# poesp_1_0.net
KiCad netlist of a schematic drawn in EAGLE
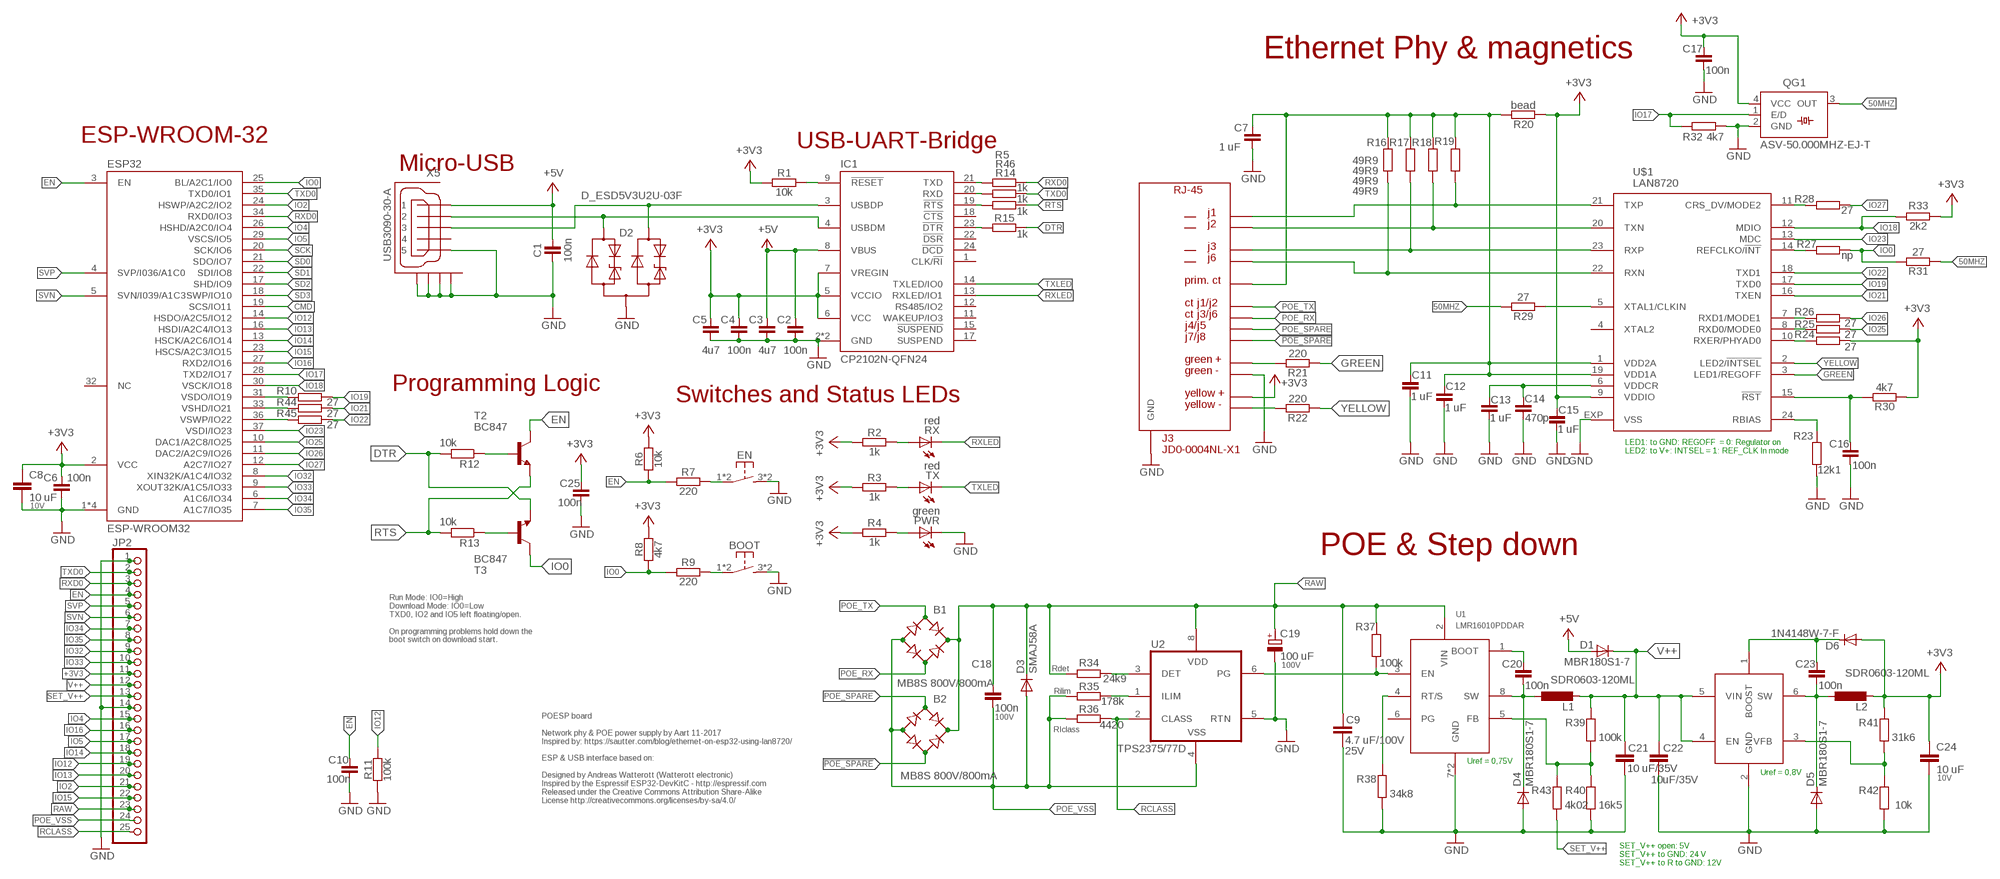
[diagram p0: schematic, sheet 1]

(export (version "E")
  (design (tool "Eeschema 10.0.6"))
  (components
    (comp (ref "B1")
      (value "MB8S 800V/800mA")
      (footprint "eagle-import:MBS")
      (libsource (lib "eagle-import") (part "BS10"))
    )
    (comp (ref "B2")
      (value "MB8S 800V/800mA")
      (footprint "eagle-import:MBS")
      (libsource (lib "eagle-import") (part "BS10"))
    )
    (comp (ref "BOOT")
      (value "SW-TACTILE-PTS840P")
      (footprint "eagle-import:PTS840P")
      (libsource (lib "eagle-import") (part "SW-TACTILE-PTS840P"))
    )
    (comp (ref "C1")
      (value "100n")
      (footprint "eagle-import:C0603")
      (libsource (lib "eagle-import") (part "CAPACITOR-0603"))
    )
    (comp (ref "C2")
      (value "100n")
      (footprint "eagle-import:C0603")
      (libsource (lib "eagle-import") (part "CAPACITOR-0603"))
    )
    (comp (ref "C3")
      (value "4u7")
      (footprint "eagle-import:C0805")
      (libsource (lib "eagle-import") (part "CAPACITOR-0805"))
    )
    (comp (ref "C4")
      (value "100n")
      (footprint "eagle-import:C0603")
      (libsource (lib "eagle-import") (part "CAPACITOR-0603"))
    )
    (comp (ref "C5")
      (value "4u7")
      (footprint "eagle-import:C0805")
      (libsource (lib "eagle-import") (part "CAPACITOR-0805"))
    )
    (comp (ref "C6")
      (value "100n")
      (footprint "eagle-import:C0603")
      (libsource (lib "eagle-import") (part "CAPACITOR-0603"))
    )
    (comp (ref "C7")
      (value "1 uF")
      (footprint "eagle-import:C0603")
      (libsource (lib "eagle-import") (part "CAPACITOR-0603"))
    )
    (comp (ref "C8")
      (value "10 uF")
      (footprint "eagle-import:C0805K")
      (fields (field (name "VOLTAGE") "10V"))
      (libsource (lib "eagle-import") (part "C-EUC0805K"))
    )
    (comp (ref "C9")
      (value "4.7 uF/100V")
      (footprint "eagle-import:C1210K")
      (fields (field (name "VOLTAGE") "25V"))
      (libsource (lib "eagle-import") (part "C-EUC1210K"))
    )
    (comp (ref "C10")
      (value "100n")
      (footprint "eagle-import:C0603")
      (libsource (lib "eagle-import") (part "CAPACITOR-0603"))
    )
    (comp (ref "C11")
      (value "1 uF")
      (footprint "eagle-import:C0603")
      (libsource (lib "eagle-import") (part "CAPACITOR-0603"))
    )
    (comp (ref "C12")
      (value "1 uF")
      (footprint "eagle-import:C0603")
      (libsource (lib "eagle-import") (part "CAPACITOR-0603"))
    )
    (comp (ref "C13")
      (value "1 uF")
      (footprint "eagle-import:C0603")
      (libsource (lib "eagle-import") (part "CAPACITOR-0603"))
    )
    (comp (ref "C14")
      (value "470p")
      (footprint "eagle-import:C0603")
      (libsource (lib "eagle-import") (part "CAPACITOR-0603"))
    )
    (comp (ref "C15")
      (value "1 uF")
      (footprint "eagle-import:C0603")
      (libsource (lib "eagle-import") (part "CAPACITOR-0603"))
    )
    (comp (ref "C16")
      (value "100n")
      (footprint "eagle-import:C0603")
      (libsource (lib "eagle-import") (part "CAPACITOR-0603"))
    )
    (comp (ref "C17")
      (value "100n")
      (footprint "eagle-import:C0603")
      (libsource (lib "eagle-import") (part "CAPACITOR-0603"))
    )
    (comp (ref "C18")
      (value "100n")
      (footprint "eagle-import:C0603")
      (fields (field (name "VOLTAGE") "100V"))
      (libsource (lib "eagle-import") (part "CAPACITOR-0603"))
    )
    (comp (ref "C19")
      (value "100 uF")
      (footprint "eagle-import:E5-10,5")
      (fields (field (name "VOLTAGE") "100V"))
      (libsource (lib "eagle-import") (part "CPOL-EUE5-10.5"))
    )
    (comp (ref "C20")
      (value "100n")
      (footprint "eagle-import:C0603")
      (libsource (lib "eagle-import") (part "CAPACITOR-0603"))
    )
    (comp (ref "C21")
      (value "10 uF/35V")
      (footprint "eagle-import:C1210K")
      (fields (field (name "VOLTAGE") "25V"))
      (libsource (lib "eagle-import") (part "C-EUC1210K"))
    )
    (comp (ref "C22")
      (value "10uF/35V")
      (footprint "eagle-import:C1210K")
      (fields (field (name "VOLTAGE") "25V"))
      (libsource (lib "eagle-import") (part "C-EUC1210K"))
    )
    (comp (ref "C23")
      (value "100n")
      (footprint "eagle-import:C0603")
      (libsource (lib "eagle-import") (part "CAPACITOR-0603"))
    )
    (comp (ref "C24")
      (value "10 uF")
      (footprint "eagle-import:C0805K")
      (fields (field (name "VOLTAGE") "10V"))
      (libsource (lib "eagle-import") (part "C-EUC0805K"))
    )
    (comp (ref "C25")
      (value "100n")
      (footprint "eagle-import:C0603")
      (libsource (lib "eagle-import") (part "CAPACITOR-0603"))
    )
    (comp (ref "D1")
      (value "MBR180S1-7")
      (footprint "eagle-import:SOD-123_MINI-SMA")
      (libsource (lib "eagle-import") (part "CGRM400-G1"))
    )
    (comp (ref "D2")
      (value "D_ESD5V3U2U-03F")
      (footprint "eagle-import:SOT723")
      (libsource (lib "eagle-import") (part "D_ESD5V3U2U-03F"))
    )
    (comp (ref "D3")
      (value "SMAJ58A")
      (footprint "eagle-import:DO214AC")
      (libsource (lib "eagle-import") (part "DIODE-DO214AC"))
    )
    (comp (ref "D4")
      (value "MBR180S1-7")
      (footprint "eagle-import:SOD-123_MINI-SMA")
      (libsource (lib "eagle-import") (part "CGRM400-G1"))
    )
    (comp (ref "D5")
      (value "MBR180S1-7")
      (footprint "eagle-import:SOD-123_MINI-SMA")
      (libsource (lib "eagle-import") (part "CGRM400-G1"))
    )
    (comp (ref "D6")
      (value "1N4148W-7-F")
      (footprint "eagle-import:SOD-123_MINI-SMA")
      (libsource (lib "eagle-import") (part "CGRM400-G1"))
    )
    (comp (ref "EN")
      (value "SW-TACTILE-PTS840P")
      (footprint "eagle-import:PTS840P")
      (libsource (lib "eagle-import") (part "SW-TACTILE-PTS840P"))
    )
    (comp (ref "ESP32")
      (value "ESP-WROOM32")
      (footprint "eagle-import:ESP-WROOM32")
      (libsource (lib "eagle-import") (part "ESP-WROOM32"))
    )
    (comp (ref "IC1")
      (value "CP2102N-QFN24")
      (footprint "eagle-import:QFN24-PAD")
      (libsource (lib "eagle-import") (part "CP2102N-QFN24"))
    )
    (comp (ref "IC3")
      (value "MCP16301/H")
      (footprint "eagle-import:SOT23-6")
      (libsource (lib "eagle-import") (part "MCP16301/H"))
    )
    (comp (ref "J3")
      (value "JD0-0004NL-X1")
      (footprint "eagle-import:JD0")
      (libsource (lib "eagle-import") (part "JD0-0004NL-X1"))
    )
    (comp (ref "JP2")
      (value "PINHD-1X25")
      (footprint "eagle-import:1X25")
      (libsource (lib "eagle-import") (part "PINHD-1X25"))
    )
    (comp (ref "L1")
      (value "SDR0603-120ML")
      (footprint "eagle-import:POWER-CHOKE_WE-TPC")
      (libsource (lib "eagle-import") (part "L-EUWE-TPC"))
    )
    (comp (ref "L2")
      (value "SDR0603-120ML")
      (footprint "eagle-import:POWER-CHOKE_WE-TPC")
      (libsource (lib "eagle-import") (part "L-EUWE-TPC"))
    )
    (comp (ref "PWR")
      (value "green")
      (footprint "eagle-import:C0603")
      (libsource (lib "eagle-import") (part "LED-0603"))
    )
    (comp (ref "QG1")
      (value "ASV-50.000MHZ-EJ-T")
      (footprint "eagle-import:SM77H")
      (libsource (lib "eagle-import") (part "SM77H"))
    )
    (comp (ref "R1")
      (value "10k")
      (footprint "eagle-import:C0603")
      (libsource (lib "eagle-import") (part "RESISTOR-0603"))
    )
    (comp (ref "R2")
      (value "1k")
      (footprint "eagle-import:C0603")
      (libsource (lib "eagle-import") (part "RESISTOR-0603"))
    )
    (comp (ref "R3")
      (value "1k")
      (footprint "eagle-import:C0603")
      (libsource (lib "eagle-import") (part "RESISTOR-0603"))
    )
    (comp (ref "R4")
      (value "1k")
      (footprint "eagle-import:C0603")
      (libsource (lib "eagle-import") (part "RESISTOR-0603"))
    )
    (comp (ref "R5")
      (value "1k")
      (footprint "eagle-import:C0603")
      (libsource (lib "eagle-import") (part "RESISTOR-0603"))
    )
    (comp (ref "R6")
      (value "10k")
      (footprint "eagle-import:C0603")
      (libsource (lib "eagle-import") (part "RESISTOR-0603"))
    )
    (comp (ref "R7")
      (value "220")
      (footprint "eagle-import:C0603")
      (libsource (lib "eagle-import") (part "RESISTOR-0603"))
    )
    (comp (ref "R8")
      (value "4k7")
      (footprint "eagle-import:C0603")
      (libsource (lib "eagle-import") (part "RESISTOR-0603"))
    )
    (comp (ref "R9")
      (value "220")
      (footprint "eagle-import:C0603")
      (libsource (lib "eagle-import") (part "RESISTOR-0603"))
    )
    (comp (ref "R10")
      (value "27")
      (footprint "eagle-import:C0603")
      (libsource (lib "eagle-import") (part "RESISTOR-0603"))
    )
    (comp (ref "R11")
      (value "100k")
      (footprint "eagle-import:C0603")
      (libsource (lib "eagle-import") (part "RESISTOR-0603"))
    )
    (comp (ref "R12")
      (value "10k")
      (footprint "eagle-import:R0603")
      (libsource (lib "eagle-import") (part "R-EU_R0603"))
    )
    (comp (ref "R13")
      (value "10k")
      (footprint "eagle-import:R0603")
      (libsource (lib "eagle-import") (part "R-EU_R0603"))
    )
    (comp (ref "R14")
      (value "1k")
      (footprint "eagle-import:C0603")
      (libsource (lib "eagle-import") (part "RESISTOR-0603"))
    )
    (comp (ref "R15")
      (value "1k")
      (footprint "eagle-import:C0603")
      (libsource (lib "eagle-import") (part "RESISTOR-0603"))
    )
    (comp (ref "R16")
      (value "49R9")
      (footprint "eagle-import:C0603")
      (libsource (lib "eagle-import") (part "RESISTOR-0603"))
    )
    (comp (ref "R17")
      (value "49R9")
      (footprint "eagle-import:C0603")
      (libsource (lib "eagle-import") (part "RESISTOR-0603"))
    )
    (comp (ref "R18")
      (value "49R9")
      (footprint "eagle-import:C0603")
      (libsource (lib "eagle-import") (part "RESISTOR-0603"))
    )
    (comp (ref "R19")
      (value "49R9")
      (footprint "eagle-import:C0603")
      (libsource (lib "eagle-import") (part "RESISTOR-0603"))
    )
    (comp (ref "R20")
      (value "bead")
      (footprint "eagle-import:C0603")
      (libsource (lib "eagle-import") (part "RESISTOR-0603"))
    )
    (comp (ref "R21")
      (value "220")
      (footprint "eagle-import:C0603")
      (libsource (lib "eagle-import") (part "RESISTOR-0603"))
    )
    (comp (ref "R22")
      (value "220")
      (footprint "eagle-import:C0603")
      (libsource (lib "eagle-import") (part "RESISTOR-0603"))
    )
    (comp (ref "R23")
      (value "12k1")
      (footprint "eagle-import:C0603")
      (libsource (lib "eagle-import") (part "RESISTOR-0603"))
    )
    (comp (ref "R24")
      (value "27")
      (footprint "eagle-import:C0603")
      (libsource (lib "eagle-import") (part "RESISTOR-0603"))
    )
    (comp (ref "R25")
      (value "27")
      (footprint "eagle-import:C0603")
      (libsource (lib "eagle-import") (part "RESISTOR-0603"))
    )
    (comp (ref "R26")
      (value "27")
      (footprint "eagle-import:C0603")
      (libsource (lib "eagle-import") (part "RESISTOR-0603"))
    )
    (comp (ref "R27")
      (value "np")
      (footprint "eagle-import:C0603")
      (libsource (lib "eagle-import") (part "RESISTOR-0603"))
    )
    (comp (ref "R28")
      (value "27")
      (footprint "eagle-import:C0603")
      (libsource (lib "eagle-import") (part "RESISTOR-0603"))
    )
    (comp (ref "R29")
      (value "27")
      (footprint "eagle-import:C0603")
      (libsource (lib "eagle-import") (part "RESISTOR-0603"))
    )
    (comp (ref "R30")
      (value "4k7")
      (footprint "eagle-import:C0603")
      (libsource (lib "eagle-import") (part "RESISTOR-0603"))
    )
    (comp (ref "R31")
      (value "27")
      (footprint "eagle-import:C0603")
      (libsource (lib "eagle-import") (part "RESISTOR-0603"))
    )
    (comp (ref "R32")
      (value "4k7")
      (footprint "eagle-import:C0603")
      (libsource (lib "eagle-import") (part "RESISTOR-0603"))
    )
    (comp (ref "R33")
      (value "2k2")
      (footprint "eagle-import:C0603")
      (libsource (lib "eagle-import") (part "RESISTOR-0603"))
    )
    (comp (ref "R34")
      (value "24k9")
      (footprint "eagle-import:C0603")
      (fields (field (name "FUNCTION") "Rdet"))
      (libsource (lib "eagle-import") (part "RESISTOR-0603"))
    )
    (comp (ref "R35")
      (value "178k")
      (footprint "eagle-import:C0603")
      (fields (field (name "FUNCTION") "Rilim"))
      (libsource (lib "eagle-import") (part "RESISTOR-0603"))
    )
    (comp (ref "R36")
      (value "4420")
      (footprint "eagle-import:C0603")
      (fields (field (name "FUNCTION") "RIclass"))
      (libsource (lib "eagle-import") (part "RESISTOR-0603"))
    )
    (comp (ref "R37")
      (value "100k")
      (footprint "eagle-import:C0603")
      (libsource (lib "eagle-import") (part "RESISTOR-0603"))
    )
    (comp (ref "R38")
      (value "34k8")
      (footprint "eagle-import:C0603")
      (fields (field (name "FUNCTION") "Rdet"))
      (libsource (lib "eagle-import") (part "RESISTOR-0603"))
    )
    (comp (ref "R39")
      (value "100k")
      (footprint "eagle-import:C0603")
      (fields (field (name "FUNCTION") "Rdet"))
      (libsource (lib "eagle-import") (part "RESISTOR-0603"))
    )
    (comp (ref "R40")
      (value "16k5")
      (footprint "eagle-import:C0603")
      (fields (field (name "FUNCTION") "Rdet"))
      (libsource (lib "eagle-import") (part "RESISTOR-0603"))
    )
    (comp (ref "R41")
      (value "31k6")
      (footprint "eagle-import:C0603")
      (fields (field (name "FUNCTION") "Rdet"))
      (libsource (lib "eagle-import") (part "RESISTOR-0603"))
    )
    (comp (ref "R42")
      (value "10k")
      (footprint "eagle-import:C0603")
      (fields (field (name "FUNCTION") "Rdet"))
      (libsource (lib "eagle-import") (part "RESISTOR-0603"))
    )
    (comp (ref "R43")
      (value "4k02")
      (footprint "eagle-import:C0603")
      (fields (field (name "FUNCTION") "Rdet"))
      (libsource (lib "eagle-import") (part "RESISTOR-0603"))
    )
    (comp (ref "R44")
      (value "27")
      (footprint "eagle-import:C0603")
      (libsource (lib "eagle-import") (part "RESISTOR-0603"))
    )
    (comp (ref "R45")
      (value "27")
      (footprint "eagle-import:C0603")
      (libsource (lib "eagle-import") (part "RESISTOR-0603"))
    )
    (comp (ref "R46")
      (value "1k")
      (footprint "eagle-import:C0603")
      (libsource (lib "eagle-import") (part "RESISTOR-0603"))
    )
    (comp (ref "RX")
      (value "red")
      (footprint "eagle-import:C0603")
      (libsource (lib "eagle-import") (part "LED-0603"))
    )
    (comp (ref "T2")
      (value "BC847")
      (footprint "eagle-import:SOT23")
      (libsource (lib "eagle-import") (part "BC847"))
    )
    (comp (ref "T3")
      (value "BC847")
      (footprint "eagle-import:SOT23")
      (libsource (lib "eagle-import") (part "BC847"))
    )
    (comp (ref "TX")
      (value "red")
      (footprint "eagle-import:C0603")
      (libsource (lib "eagle-import") (part "LED-0603"))
    )
    (comp (ref "U$1")
      (value "LAN8720")
      (footprint "eagle-import:QFN24")
      (libsource (lib "eagle-import") (part "LAN8720"))
    )
    (comp (ref "U1")
      (value "LMR16010PDDAR")
      (footprint "eagle-import:HSOIC8")
      (libsource (lib "eagle-import") (part "LMR16010PDDAR"))
    )
    (comp (ref "U2")
      (value "TPS2375/77D")
      (footprint "eagle-import:SO08")
      (libsource (lib "eagle-import") (part "TPS2375/77D"))
    )
    (comp (ref "X5")
      (value "USB3090-30-A")
      (footprint "eagle-import:USB3090-30-A")
      (libsource (lib "eagle-import") (part "USB3090-30-A"))
    )
  )
  (nets
    (net (code "1") (name "+3V3") (class "Default")
      (node (ref "C15") (pin "2") (pinfunction "2_2") (pintype "passive"))
      (node (ref "C17") (pin "2") (pinfunction "2_2") (pintype "passive"))
      (node (ref "C24") (pin "1") (pinfunction "1_1") (pintype "passive"))
      (node (ref "C25") (pin "2") (pinfunction "2_2") (pintype "passive"))
      (node (ref "C4") (pin "2") (pinfunction "2_2") (pintype "passive"))
      (node (ref "C5") (pin "2") (pinfunction "2_2") (pintype "passive"))
      (node (ref "C6") (pin "2") (pinfunction "2_2") (pintype "passive"))
      (node (ref "C8") (pin "1") (pinfunction "1_1") (pintype "passive"))
      (node (ref "D6") (pin "A") (pinfunction "A_A") (pintype "passive"))
      (node (ref "ESP32") (pin "2") (pinfunction "VCC_2") (pintype "power_in"))
      (node (ref "IC1") (pin "5") (pinfunction "VCCIO_5") (pintype "power_in"))
      (node (ref "IC1") (pin "6") (pinfunction "VCC_6") (pintype "power_in"))
      (node (ref "IC1") (pin "7") (pinfunction "VREGIN_7") (pintype "power_in"))
      (node (ref "J3") (pin "P$14") (pinfunction "P$14_P$14") (pintype "bidirectional"))
      (node (ref "JP2") (pin "11") (pinfunction "11_11") (pintype "passive"))
      (node (ref "L2") (pin "2") (pinfunction "2_2") (pintype "passive"))
      (node (ref "QG1") (pin "4") (pinfunction "VCC_4") (pintype "power_in"))
      (node (ref "R1") (pin "1") (pinfunction "1_1") (pintype "passive"))
      (node (ref "R2") (pin "1") (pinfunction "1_1") (pintype "passive"))
      (node (ref "R20") (pin "1") (pinfunction "1_1") (pintype "passive"))
      (node (ref "R24") (pin "1") (pinfunction "1_1") (pintype "passive"))
      (node (ref "R3") (pin "1") (pinfunction "1_1") (pintype "passive"))
      (node (ref "R30") (pin "1") (pinfunction "1_1") (pintype "passive"))
      (node (ref "R33") (pin "1") (pinfunction "1_1") (pintype "passive"))
      (node (ref "R4") (pin "1") (pinfunction "1_1") (pintype "passive"))
      (node (ref "R41") (pin "1") (pinfunction "1_1") (pintype "passive"))
      (node (ref "R6") (pin "2") (pinfunction "2_2") (pintype "passive"))
      (node (ref "R8") (pin "2") (pinfunction "2_2") (pintype "passive"))
      (node (ref "U$1") (pin "9") (pinfunction "VDDIO_9") (pintype "power_in"))
    )
    (net (code "2") (name "+5V") (class "Default")
      (node (ref "C1") (pin "2") (pinfunction "2_2") (pintype "passive"))
      (node (ref "C2") (pin "2") (pinfunction "2_2") (pintype "passive"))
      (node (ref "C3") (pin "2") (pinfunction "2_2") (pintype "passive"))
      (node (ref "D1") (pin "A") (pinfunction "A_A") (pintype "passive"))
      (node (ref "IC1") (pin "8") (pinfunction "VBUS_8") (pintype "power_in"))
      (node (ref "X5") (pin "1") (pinfunction "1_1") (pintype "input"))
    )
    (net (code "3") (name "/~{POE_SPARE}") (class "Default")
      (node (ref "B2") (pin "AC2") (pinfunction "AC2_AC2") (pintype "passive"))
      (node (ref "J3") (pin "P$8") (pinfunction "P$8_P$8") (pintype "bidirectional"))
    )
    (net (code "4") (name "50MHZ") (class "Default")
      (node (ref "QG1") (pin "3") (pinfunction "OUT_3") (pintype "output"))
      (node (ref "R29") (pin "2") (pinfunction "2_2") (pintype "passive"))
      (node (ref "R31") (pin "1") (pinfunction "1_1") (pintype "passive"))
    )
    (net (code "5") (name "CMD") (class "Default")
      (node (ref "ESP32") (pin "19") (pinfunction "SCS/IO11_19") (pintype "bidirectional"))
    )
    (net (code "6") (name "DTR") (class "Default")
      (node (ref "R12") (pin "2") (pinfunction "2_2") (pintype "passive"))
      (node (ref "R15") (pin "2") (pinfunction "2_2") (pintype "passive"))
      (node (ref "T3") (pin "2") (pinfunction "E_2") (pintype "passive"))
    )
    (net (code "7") (name "EN") (class "Default")
      (node (ref "C10") (pin "2") (pinfunction "2_2") (pintype "passive"))
      (node (ref "ESP32") (pin "3") (pinfunction "EN_3") (pintype "bidirectional"))
      (node (ref "JP2") (pin "4") (pinfunction "4_4") (pintype "passive"))
      (node (ref "R6") (pin "1") (pinfunction "1_1") (pintype "passive"))
      (node (ref "R7") (pin "1") (pinfunction "1_1") (pintype "passive"))
      (node (ref "T2") (pin "3") (pinfunction "C_3") (pintype "passive"))
    )
    (net (code "8") (name "GND") (class "Default")
      (node (ref "BOOT") (pin "3") (pinfunction "S1_3") (pintype "passive"))
      (node (ref "BOOT") (pin "4") (pinfunction "S1_4") (pintype "passive"))
      (node (ref "C1") (pin "1") (pinfunction "1_1") (pintype "passive"))
      (node (ref "C10") (pin "1") (pinfunction "1_1") (pintype "passive"))
      (node (ref "C11") (pin "1") (pinfunction "1_1") (pintype "passive"))
      (node (ref "C12") (pin "1") (pinfunction "1_1") (pintype "passive"))
      (node (ref "C13") (pin "1") (pinfunction "1_1") (pintype "passive"))
      (node (ref "C14") (pin "1") (pinfunction "1_1") (pintype "passive"))
      (node (ref "C15") (pin "1") (pinfunction "1_1") (pintype "passive"))
      (node (ref "C16") (pin "1") (pinfunction "1_1") (pintype "passive"))
      (node (ref "C17") (pin "1") (pinfunction "1_1") (pintype "passive"))
      (node (ref "C19") (pin "-") (pinfunction "-_-") (pintype "passive"))
      (node (ref "C2") (pin "1") (pinfunction "1_1") (pintype "passive"))
      (node (ref "C21") (pin "2") (pinfunction "2_2") (pintype "passive"))
      (node (ref "C22") (pin "2") (pinfunction "2_2") (pintype "passive"))
      (node (ref "C24") (pin "2") (pinfunction "2_2") (pintype "passive"))
      (node (ref "C25") (pin "1") (pinfunction "1_1") (pintype "passive"))
      (node (ref "C3") (pin "1") (pinfunction "1_1") (pintype "passive"))
      (node (ref "C4") (pin "1") (pinfunction "1_1") (pintype "passive"))
      (node (ref "C5") (pin "1") (pinfunction "1_1") (pintype "passive"))
      (node (ref "C6") (pin "1") (pinfunction "1_1") (pintype "passive"))
      (node (ref "C7") (pin "1") (pinfunction "1_1") (pintype "passive"))
      (node (ref "C8") (pin "2") (pinfunction "2_2") (pintype "passive"))
      (node (ref "C9") (pin "2") (pinfunction "2_2") (pintype "passive"))
      (node (ref "D2") (pin "3") (pinfunction "A_3") (pintype "passive"))
      (node (ref "D4") (pin "A") (pinfunction "A_A") (pintype "passive"))
      (node (ref "D5") (pin "A") (pinfunction "A_A") (pintype "passive"))
      (node (ref "EN") (pin "3") (pinfunction "S1_3") (pintype "passive"))
      (node (ref "EN") (pin "4") (pinfunction "S1_4") (pintype "passive"))
      (node (ref "ESP32") (pin "1") (pinfunction "GND_1") (pintype "power_in"))
      (node (ref "ESP32") (pin "15") (pinfunction "GND_15") (pintype "power_in"))
      (node (ref "ESP32") (pin "38") (pinfunction "GND_38") (pintype "power_in"))
      (node (ref "ESP32") (pin "TP") (pinfunction "GND_TP") (pintype "power_in"))
      (node (ref "IC1") (pin "2") (pinfunction "GND_2") (pintype "power_in"))
      (node (ref "IC1") (pin "TP") (pinfunction "GND_TP") (pintype "power_in"))
      (node (ref "IC3") (pin "2") (pinfunction "GND_2") (pintype "power_in"))
      (node (ref "J3") (pin "P$11") (pinfunction "P$11_P$11") (pintype "bidirectional"))
      (node (ref "J3") (pin "P$21") (pinfunction "GND_P$21") (pintype "bidirectional"))
      (node (ref "J3") (pin "P$22") (pinfunction "GND_P$22") (pintype "bidirectional"))
      (node (ref "J3") (pin "P$23") (pinfunction "GND_P$23") (pintype "bidirectional"))
      (node (ref "J3") (pin "P$24") (pinfunction "GND_P$24") (pintype "bidirectional"))
      (node (ref "JP2") (pin "1") (pinfunction "1_1") (pintype "passive"))
      (node (ref "JP2") (pin "14") (pinfunction "14_14") (pintype "passive"))
      (node (ref "PWR") (pin "C") (pinfunction "C_C") (pintype "passive"))
      (node (ref "QG1") (pin "2") (pinfunction "GND_2") (pintype "power_in"))
      (node (ref "R11") (pin "1") (pinfunction "1_1") (pintype "passive"))
      (node (ref "R23") (pin "1") (pinfunction "1_1") (pintype "passive"))
      (node (ref "R32") (pin "1") (pinfunction "1_1") (pintype "passive"))
      (node (ref "R38") (pin "2") (pinfunction "2_2") (pintype "passive"))
      (node (ref "R40") (pin "2") (pinfunction "2_2") (pintype "passive"))
      (node (ref "R42") (pin "2") (pinfunction "2_2") (pintype "passive"))
      (node (ref "U$1") (pin "EXP") (pinfunction "VSS_EXP") (pintype "power_in"))
      (node (ref "U1") (pin "7") (pinfunction "GND_7") (pintype "bidirectional"))
      (node (ref "U1") (pin "P$9") (pinfunction "GND_P$9") (pintype "bidirectional"))
      (node (ref "U2") (pin "5") (pinfunction "RTN_5") (pintype "output"))
      (node (ref "X5") (pin "5") (pinfunction "5_5") (pintype "input"))
      (node (ref "X5") (pin "GND2") (pinfunction "GND1_GND2") (pintype "bidirectional"))
      (node (ref "X5") (pin "GND3") (pinfunction "GND2_GND3") (pintype "bidirectional"))
      (node (ref "X5") (pin "P$1") (pinfunction "GND3_P$1") (pintype "bidirectional"))
      (node (ref "X5") (pin "P$2") (pinfunction "GND4_P$2") (pintype "bidirectional"))
    )
    (net (code "9") (name "GREEN") (class "Default")
      (node (ref "R21") (pin "1") (pinfunction "1_1") (pintype "passive"))
      (node (ref "U$1") (pin "3") (pinfunction "LED1/REGOFF_3") (pintype "bidirectional"))
    )
    (net (code "10") (name "IO0") (class "Default")
      (node (ref "ESP32") (pin "25") (pinfunction "BL/A2C1/IO0_25") (pintype "bidirectional"))
      (node (ref "R27") (pin "1") (pinfunction "1_1") (pintype "passive"))
      (node (ref "R31") (pin "2") (pinfunction "2_2") (pintype "passive"))
      (node (ref "R8") (pin "1") (pinfunction "1_1") (pintype "passive"))
      (node (ref "R9") (pin "1") (pinfunction "1_1") (pintype "passive"))
      (node (ref "T3") (pin "3") (pinfunction "C_3") (pintype "passive"))
    )
    (net (code "11") (name "IO2") (class "Default")
      (node (ref "ESP32") (pin "24") (pinfunction "HSWP/A2C2/IO2_24") (pintype "bidirectional"))
      (node (ref "JP2") (pin "21") (pinfunction "21_21") (pintype "passive"))
    )
    (net (code "12") (name "IO4") (class "Default")
      (node (ref "ESP32") (pin "26") (pinfunction "HSHD/A2C0/IO4_26") (pintype "bidirectional"))
      (node (ref "JP2") (pin "15") (pinfunction "15_15") (pintype "passive"))
    )
    (net (code "13") (name "IO5") (class "Default")
      (node (ref "ESP32") (pin "29") (pinfunction "VSCS/IO5_29") (pintype "bidirectional"))
      (node (ref "JP2") (pin "17") (pinfunction "17_17") (pintype "passive"))
    )
    (net (code "14") (name "IO12") (class "Default")
      (node (ref "ESP32") (pin "14") (pinfunction "HSDO/A2C5/IO12_14") (pintype "bidirectional"))
      (node (ref "JP2") (pin "19") (pinfunction "19_19") (pintype "passive"))
      (node (ref "R11") (pin "2") (pinfunction "2_2") (pintype "passive"))
    )
    (net (code "15") (name "IO13") (class "Default")
      (node (ref "ESP32") (pin "16") (pinfunction "HSDI/A2C4/IO13_16") (pintype "bidirectional"))
      (node (ref "JP2") (pin "20") (pinfunction "20_20") (pintype "passive"))
    )
    (net (code "16") (name "IO14") (class "Default")
      (node (ref "ESP32") (pin "13") (pinfunction "HSCK/A2C6/IO14_13") (pintype "bidirectional"))
      (node (ref "JP2") (pin "18") (pinfunction "18_18") (pintype "passive"))
    )
    (net (code "17") (name "IO15") (class "Default")
      (node (ref "ESP32") (pin "23") (pinfunction "HSCS/A2C3/IO15_23") (pintype "bidirectional"))
      (node (ref "JP2") (pin "22") (pinfunction "22_22") (pintype "passive"))
    )
    (net (code "18") (name "IO16") (class "Default")
      (node (ref "ESP32") (pin "27") (pinfunction "RXD2/IO16_27") (pintype "bidirectional"))
      (node (ref "JP2") (pin "16") (pinfunction "16_16") (pintype "passive"))
    )
    (net (code "19") (name "IO17") (class "Default")
      (node (ref "ESP32") (pin "28") (pinfunction "TXD2/IO17_28") (pintype "bidirectional"))
      (node (ref "QG1") (pin "1") (pinfunction "E/D_1") (pintype "input"))
      (node (ref "R32") (pin "2") (pinfunction "2_2") (pintype "passive"))
    )
    (net (code "20") (name "IO18") (class "Default")
      (node (ref "ESP32") (pin "30") (pinfunction "VSCK/IO18_30") (pintype "bidirectional"))
      (node (ref "R33") (pin "2") (pinfunction "2_2") (pintype "passive"))
      (node (ref "U$1") (pin "12") (pinfunction "MDIO_12") (pintype "bidirectional"))
    )
    (net (code "21") (name "IO19") (class "Default")
      (node (ref "R10") (pin "1") (pinfunction "1_1") (pintype "passive"))
      (node (ref "U$1") (pin "17") (pinfunction "TXD0_17") (pintype "bidirectional"))
    )
    (net (code "22") (name "IO21") (class "Default")
      (node (ref "R44") (pin "1") (pinfunction "1_1") (pintype "passive"))
      (node (ref "U$1") (pin "16") (pinfunction "TXEN_16") (pintype "bidirectional"))
    )
    (net (code "23") (name "IO22") (class "Default")
      (node (ref "R45") (pin "1") (pinfunction "1_1") (pintype "passive"))
      (node (ref "U$1") (pin "18") (pinfunction "TXD1_18") (pintype "bidirectional"))
    )
    (net (code "24") (name "IO23") (class "Default")
      (node (ref "ESP32") (pin "37") (pinfunction "VSDI/IO23_37") (pintype "bidirectional"))
      (node (ref "U$1") (pin "13") (pinfunction "MDC_13") (pintype "bidirectional"))
    )
    (net (code "25") (name "IO25") (class "Default")
      (node (ref "ESP32") (pin "10") (pinfunction "DAC1/A2C8/IO25_10") (pintype "bidirectional"))
      (node (ref "R25") (pin "1") (pinfunction "1_1") (pintype "passive"))
    )
    (net (code "26") (name "IO26") (class "Default")
      (node (ref "ESP32") (pin "11") (pinfunction "DAC2/A2C9/IO26_11") (pintype "bidirectional"))
      (node (ref "R26") (pin "1") (pinfunction "1_1") (pintype "passive"))
    )
    (net (code "27") (name "IO27") (class "Default")
      (node (ref "ESP32") (pin "12") (pinfunction "A2C7/IO27_12") (pintype "bidirectional"))
      (node (ref "R28") (pin "1") (pinfunction "1_1") (pintype "passive"))
    )
    (net (code "28") (name "IO32") (class "Default")
      (node (ref "ESP32") (pin "8") (pinfunction "XIN32K/A1C4/IO32_8") (pintype "bidirectional"))
      (node (ref "JP2") (pin "9") (pinfunction "9_9") (pintype "passive"))
    )
    (net (code "29") (name "IO33") (class "Default")
      (node (ref "ESP32") (pin "9") (pinfunction "XOUT32K/A1C5/IO33_9") (pintype "bidirectional"))
      (node (ref "JP2") (pin "10") (pinfunction "10_10") (pintype "passive"))
    )
    (net (code "30") (name "IO34") (class "Default")
      (node (ref "ESP32") (pin "6") (pinfunction "A1C6/IO34_6") (pintype "bidirectional"))
      (node (ref "JP2") (pin "7") (pinfunction "7_7") (pintype "passive"))
    )
    (net (code "31") (name "IO35") (class "Default")
      (node (ref "ESP32") (pin "7") (pinfunction "A1C7/IO35_7") (pintype "bidirectional"))
      (node (ref "JP2") (pin "8") (pinfunction "8_8") (pintype "passive"))
    )
    (net (code "32") (name "Net-(BOOT-P1-Pad1)") (class "Default")
      (node (ref "BOOT") (pin "1") (pinfunction "P1_1") (pintype "passive"))
      (node (ref "BOOT") (pin "2") (pinfunction "P1_2") (pintype "passive"))
      (node (ref "R9") (pin "2") (pinfunction "2_2") (pintype "passive"))
    )
    (net (code "33") (name "Net-(D2-C1)") (class "Default")
      (node (ref "D2") (pin "1") (pinfunction "C1_1") (pintype "passive"))
      (node (ref "IC1") (pin "4") (pinfunction "USBDM_4") (pintype "bidirectional"))
      (node (ref "X5") (pin "2") (pinfunction "2_2") (pintype "input"))
    )
    (net (code "34") (name "Net-(D2-C2)") (class "Default")
      (node (ref "D2") (pin "2") (pinfunction "C2_2") (pintype "passive"))
      (node (ref "IC1") (pin "3") (pinfunction "USBDP_3") (pintype "bidirectional"))
      (node (ref "X5") (pin "3") (pinfunction "3_3") (pintype "input"))
    )
    (net (code "35") (name "Net-(EN-P1-Pad1)") (class "Default")
      (node (ref "EN") (pin "1") (pinfunction "P1_1") (pintype "passive"))
      (node (ref "EN") (pin "2") (pinfunction "P1_2") (pintype "passive"))
      (node (ref "R7") (pin "2") (pinfunction "2_2") (pintype "passive"))
    )
    (net (code "36") (name "Net-(ESP32-VSDO{slash}IO19)") (class "Default")
      (node (ref "ESP32") (pin "31") (pinfunction "VSDO/IO19_31") (pintype "bidirectional"))
      (node (ref "R10") (pin "2") (pinfunction "2_2") (pintype "passive"))
    )
    (net (code "37") (name "Net-(ESP32-VSHD{slash}IO21)") (class "Default")
      (node (ref "ESP32") (pin "33") (pinfunction "VSHD/IO21_33") (pintype "bidirectional"))
      (node (ref "R44") (pin "2") (pinfunction "2_2") (pintype "passive"))
    )
    (net (code "38") (name "Net-(ESP32-VSWP{slash}IO22)") (class "Default")
      (node (ref "ESP32") (pin "36") (pinfunction "VSWP/IO22_36") (pintype "bidirectional"))
      (node (ref "R45") (pin "2") (pinfunction "2_2") (pintype "passive"))
    )
    (net (code "39") (name "Net-(IC1-RXD)") (class "Default")
      (node (ref "IC1") (pin "20") (pinfunction "RXD_20") (pintype "bidirectional"))
      (node (ref "R46") (pin "1") (pinfunction "1_1") (pintype "passive"))
    )
    (net (code "40") (name "Net-(IC1-TXD)") (class "Default")
      (node (ref "IC1") (pin "21") (pinfunction "TXD_21") (pintype "bidirectional"))
      (node (ref "R5") (pin "1") (pinfunction "1_1") (pintype "passive"))
    )
    (net (code "41") (name "Net-(IC1-~{DTR})") (class "Default")
      (node (ref "IC1") (pin "23") (pinfunction "~{DTR}_23") (pintype "bidirectional"))
      (node (ref "R15") (pin "1") (pinfunction "1_1") (pintype "passive"))
    )
    (net (code "42") (name "Net-(IC1-~{RESET})") (class "Default")
      (node (ref "IC1") (pin "9") (pinfunction "~{RESET}_9") (pintype "bidirectional"))
      (node (ref "R1") (pin "2") (pinfunction "2_2") (pintype "passive"))
    )
    (net (code "43") (name "Net-(IC1-~{RTS})") (class "Default")
      (node (ref "IC1") (pin "19") (pinfunction "~{RTS}_19") (pintype "bidirectional"))
      (node (ref "R14") (pin "1") (pinfunction "1_1") (pintype "passive"))
    )
    (net (code "44") (name "Net-(IC3-BOOST)") (class "Default")
      (node (ref "C23") (pin "2") (pinfunction "2_2") (pintype "passive"))
      (node (ref "D6") (pin "C") (pinfunction "C_C") (pintype "passive"))
      (node (ref "IC3") (pin "1") (pinfunction "BOOST_1") (pintype "bidirectional"))
    )
    (net (code "45") (name "Net-(IC3-SW)") (class "Default")
      (node (ref "C23") (pin "1") (pinfunction "1_1") (pintype "passive"))
      (node (ref "D5") (pin "C") (pinfunction "C_C") (pintype "passive"))
      (node (ref "IC3") (pin "6") (pinfunction "SW_6") (pintype "power_in"))
      (node (ref "L2") (pin "1") (pinfunction "1_1") (pintype "passive"))
    )
    (net (code "46") (name "Net-(IC3-VFB)") (class "Default")
      (node (ref "IC3") (pin "3") (pinfunction "VFB_3") (pintype "bidirectional"))
      (node (ref "R41") (pin "2") (pinfunction "2_2") (pintype "passive"))
      (node (ref "R42") (pin "1") (pinfunction "1_1") (pintype "passive"))
    )
    (net (code "47") (name "Net-(J3-PadP$12)") (class "Default")
      (node (ref "J3") (pin "P$12") (pinfunction "P$12_P$12") (pintype "bidirectional"))
      (node (ref "R21") (pin "2") (pinfunction "2_2") (pintype "passive"))
    )
    (net (code "48") (name "Net-(J3-PadP$13)") (class "Default")
      (node (ref "J3") (pin "P$13") (pinfunction "P$13_P$13") (pintype "bidirectional"))
      (node (ref "R22") (pin "2") (pinfunction "2_2") (pintype "passive"))
    )
    (net (code "49") (name "Net-(PWR-PadA)") (class "Default")
      (node (ref "PWR") (pin "A") (pinfunction "A_A") (pintype "passive"))
      (node (ref "R4") (pin "2") (pinfunction "2_2") (pintype "passive"))
    )
    (net (code "50") (name "Net-(R2-Pad2)") (class "Default")
      (node (ref "R2") (pin "2") (pinfunction "2_2") (pintype "passive"))
      (node (ref "RX") (pin "A") (pinfunction "A_A") (pintype "passive"))
    )
    (net (code "51") (name "Net-(R3-Pad2)") (class "Default")
      (node (ref "R3") (pin "2") (pinfunction "2_2") (pintype "passive"))
      (node (ref "TX") (pin "A") (pinfunction "A_A") (pintype "passive"))
    )
    (net (code "52") (name "Net-(T2-B)") (class "Default")
      (node (ref "R12") (pin "1") (pinfunction "1_1") (pintype "passive"))
      (node (ref "T2") (pin "1") (pinfunction "B_1") (pintype "passive"))
    )
    (net (code "53") (name "Net-(T3-B)") (class "Default")
      (node (ref "R13") (pin "1") (pinfunction "1_1") (pintype "passive"))
      (node (ref "T3") (pin "1") (pinfunction "B_1") (pintype "passive"))
    )
    (net (code "54") (name "Net-(U$1-CRS_DV{slash}MODE2)") (class "Default")
      (node (ref "R28") (pin "2") (pinfunction "2_2") (pintype "passive"))
      (node (ref "U$1") (pin "11") (pinfunction "CRS_DV/MODE2_11") (pintype "bidirectional"))
    )
    (net (code "55") (name "Net-(U$1-RBIAS)") (class "Default")
      (node (ref "R23") (pin "2") (pinfunction "2_2") (pintype "passive"))
      (node (ref "U$1") (pin "24") (pinfunction "RBIAS_24") (pintype "bidirectional"))
    )
    (net (code "56") (name "Net-(U$1-REFCLKO{slash}~{INT})") (class "Default")
      (node (ref "R27") (pin "2") (pinfunction "2_2") (pintype "passive"))
      (node (ref "U$1") (pin "14") (pinfunction "REFCLKO/~{INT}_14") (pintype "bidirectional"))
    )
    (net (code "57") (name "Net-(U$1-RXD0{slash}MODE0)") (class "Default")
      (node (ref "R25") (pin "2") (pinfunction "2_2") (pintype "passive"))
      (node (ref "U$1") (pin "8") (pinfunction "RXD0/MODE0_8") (pintype "bidirectional"))
    )
    (net (code "58") (name "Net-(U$1-RXD1{slash}MODE1)") (class "Default")
      (node (ref "R26") (pin "2") (pinfunction "2_2") (pintype "passive"))
      (node (ref "U$1") (pin "7") (pinfunction "RXD1/MODE1_7") (pintype "bidirectional"))
    )
    (net (code "59") (name "Net-(U$1-RXER{slash}PHYAD0)") (class "Default")
      (node (ref "R24") (pin "2") (pinfunction "2_2") (pintype "passive"))
      (node (ref "U$1") (pin "10") (pinfunction "RXER/PHYAD0_10") (pintype "bidirectional"))
    )
    (net (code "60") (name "Net-(U$1-RXN)") (class "Default")
      (node (ref "J3") (pin "P$5") (pinfunction "P$5_P$5") (pintype "bidirectional"))
      (node (ref "R16") (pin "1") (pinfunction "1_1") (pintype "passive"))
      (node (ref "U$1") (pin "22") (pinfunction "RXN_22") (pintype "bidirectional"))
    )
    (net (code "61") (name "Net-(U$1-RXP)") (class "Default")
      (node (ref "J3") (pin "P$3") (pinfunction "P$3_P$3") (pintype "bidirectional"))
      (node (ref "R17") (pin "1") (pinfunction "1_1") (pintype "passive"))
      (node (ref "U$1") (pin "23") (pinfunction "RXP_23") (pintype "bidirectional"))
    )
    (net (code "62") (name "Net-(U$1-TXN)") (class "Default")
      (node (ref "J3") (pin "P$2") (pinfunction "P$2_P$2") (pintype "bidirectional"))
      (node (ref "R18") (pin "1") (pinfunction "1_1") (pintype "passive"))
      (node (ref "U$1") (pin "20") (pinfunction "TXN_20") (pintype "bidirectional"))
    )
    (net (code "63") (name "Net-(U$1-TXP)") (class "Default")
      (node (ref "J3") (pin "P$1") (pinfunction "P$1_P$1") (pintype "bidirectional"))
      (node (ref "R19") (pin "1") (pinfunction "1_1") (pintype "passive"))
      (node (ref "U$1") (pin "21") (pinfunction "TXP_21") (pintype "bidirectional"))
    )
    (net (code "64") (name "Net-(U$1-VDD1A)") (class "Default")
      (node (ref "C11") (pin "2") (pinfunction "2_2") (pintype "passive"))
      (node (ref "C12") (pin "2") (pinfunction "2_2") (pintype "passive"))
      (node (ref "C7") (pin "2") (pinfunction "2_2") (pintype "passive"))
      (node (ref "J3") (pin "P$4") (pinfunction "P$4_P$4") (pintype "bidirectional"))
      (node (ref "R16") (pin "2") (pinfunction "2_2") (pintype "passive"))
      (node (ref "R17") (pin "2") (pinfunction "2_2") (pintype "passive"))
      (node (ref "R18") (pin "2") (pinfunction "2_2") (pintype "passive"))
      (node (ref "R19") (pin "2") (pinfunction "2_2") (pintype "passive"))
      (node (ref "R20") (pin "2") (pinfunction "2_2") (pintype "passive"))
      (node (ref "U$1") (pin "1") (pinfunction "VDD2A_1") (pintype "power_in"))
      (node (ref "U$1") (pin "19") (pinfunction "VDD1A_19") (pintype "power_in"))
    )
    (net (code "65") (name "Net-(U$1-VDDCR)") (class "Default")
      (node (ref "C13") (pin "2") (pinfunction "2_2") (pintype "passive"))
      (node (ref "C14") (pin "2") (pinfunction "2_2") (pintype "passive"))
      (node (ref "U$1") (pin "6") (pinfunction "VDDCR_6") (pintype "power_in"))
    )
    (net (code "66") (name "Net-(U$1-XTAL1{slash}CLKIN)") (class "Default")
      (node (ref "R29") (pin "1") (pinfunction "1_1") (pintype "passive"))
      (node (ref "U$1") (pin "5") (pinfunction "XTAL1/CLKIN_5") (pintype "bidirectional"))
    )
    (net (code "67") (name "Net-(U$1-~{RST})") (class "Default")
      (node (ref "C16") (pin "2") (pinfunction "2_2") (pintype "passive"))
      (node (ref "R30") (pin "2") (pinfunction "2_2") (pintype "passive"))
      (node (ref "U$1") (pin "15") (pinfunction "~{RST}_15") (pintype "bidirectional"))
    )
    (net (code "68") (name "Net-(U1-BOOT)") (class "Default")
      (node (ref "C20") (pin "2") (pinfunction "2_2") (pintype "passive"))
      (node (ref "U1") (pin "1") (pinfunction "BOOT_1") (pintype "bidirectional"))
    )
    (net (code "69") (name "Net-(U1-EN)") (class "Default")
      (node (ref "R37") (pin "2") (pinfunction "2_2") (pintype "passive"))
      (node (ref "U1") (pin "3") (pinfunction "EN_3") (pintype "bidirectional"))
      (node (ref "U2") (pin "6") (pinfunction "PG_6") (pintype "output"))
    )
    (net (code "70") (name "Net-(U1-FB)") (class "Default")
      (node (ref "R39") (pin "2") (pinfunction "2_2") (pintype "passive"))
      (node (ref "R40") (pin "1") (pinfunction "1_1") (pintype "passive"))
      (node (ref "R43") (pin "1") (pinfunction "1_1") (pintype "passive"))
      (node (ref "U1") (pin "5") (pinfunction "FB_5") (pintype "bidirectional"))
    )
    (net (code "71") (name "Net-(U1-RT{slash}S)") (class "Default")
      (node (ref "R38") (pin "1") (pinfunction "1_1") (pintype "passive"))
      (node (ref "U1") (pin "4") (pinfunction "RT/S_4") (pintype "bidirectional"))
    )
    (net (code "72") (name "Net-(U1-SW)") (class "Default")
      (node (ref "C20") (pin "1") (pinfunction "1_1") (pintype "passive"))
      (node (ref "D4") (pin "C") (pinfunction "C_C") (pintype "passive"))
      (node (ref "L1") (pin "1") (pinfunction "1_1") (pintype "passive"))
      (node (ref "U1") (pin "8") (pinfunction "SW_8") (pintype "bidirectional"))
    )
    (net (code "73") (name "Net-(U2-DET)") (class "Default")
      (node (ref "R34") (pin "1") (pinfunction "1_1") (pintype "passive"))
      (node (ref "U2") (pin "3") (pinfunction "DET_3") (pintype "output"))
    )
    (net (code "74") (name "Net-(U2-ILIM)") (class "Default")
      (node (ref "R35") (pin "1") (pinfunction "1_1") (pintype "passive"))
      (node (ref "U2") (pin "1") (pinfunction "ILIM_1") (pintype "output"))
    )
    (net (code "75") (name "POE_RX") (class "Default")
      (node (ref "B1") (pin "AC2") (pinfunction "AC2_AC2") (pintype "passive"))
      (node (ref "J3") (pin "P$10") (pinfunction "P$10_P$10") (pintype "bidirectional"))
    )
    (net (code "76") (name "POE_SPARE") (class "Default")
      (node (ref "B2") (pin "AC1") (pinfunction "AC1_AC1") (pintype "passive"))
      (node (ref "J3") (pin "P$7") (pinfunction "P$7_P$7") (pintype "bidirectional"))
    )
    (net (code "77") (name "POE_TX") (class "Default")
      (node (ref "B1") (pin "AC1") (pinfunction "AC1_AC1") (pintype "passive"))
      (node (ref "J3") (pin "P$9") (pinfunction "P$9_P$9") (pintype "bidirectional"))
    )
    (net (code "78") (name "POE_VSS") (class "Default")
      (node (ref "B1") (pin "-") (pinfunction "-_-") (pintype "passive"))
      (node (ref "B2") (pin "-") (pinfunction "-_-") (pintype "passive"))
      (node (ref "C18") (pin "1") (pinfunction "1_1") (pintype "passive"))
      (node (ref "D3") (pin "A") (pinfunction "A_A") (pintype "passive"))
      (node (ref "JP2") (pin "24") (pinfunction "24_24") (pintype "passive"))
      (node (ref "R35") (pin "2") (pinfunction "2_2") (pintype "passive"))
      (node (ref "R36") (pin "2") (pinfunction "2_2") (pintype "passive"))
      (node (ref "U2") (pin "4") (pinfunction "VSS_4") (pintype "power_in"))
    )
    (net (code "79") (name "RAW") (class "Default")
      (node (ref "B1") (pin "+") (pinfunction "+_+") (pintype "passive"))
      (node (ref "B2") (pin "+") (pinfunction "+_+") (pintype "passive"))
      (node (ref "C18") (pin "2") (pinfunction "2_2") (pintype "passive"))
      (node (ref "C19") (pin "+") (pinfunction "+_+") (pintype "passive"))
      (node (ref "C9") (pin "1") (pinfunction "1_1") (pintype "passive"))
      (node (ref "D3") (pin "C") (pinfunction "C_C") (pintype "passive"))
      (node (ref "JP2") (pin "23") (pinfunction "23_23") (pintype "passive"))
      (node (ref "R34") (pin "2") (pinfunction "2_2") (pintype "passive"))
      (node (ref "R37") (pin "1") (pinfunction "1_1") (pintype "passive"))
      (node (ref "U1") (pin "2") (pinfunction "VIN_2") (pintype "bidirectional"))
      (node (ref "U2") (pin "8") (pinfunction "VDD_8") (pintype "power_in"))
    )
    (net (code "80") (name "RCLASS") (class "Default")
      (node (ref "JP2") (pin "25") (pinfunction "25_25") (pintype "passive"))
      (node (ref "R36") (pin "1") (pinfunction "1_1") (pintype "passive"))
      (node (ref "U2") (pin "2") (pinfunction "CLASS_2") (pintype "output"))
    )
    (net (code "81") (name "RTS") (class "Default")
      (node (ref "R13") (pin "2") (pinfunction "2_2") (pintype "passive"))
      (node (ref "R14") (pin "2") (pinfunction "2_2") (pintype "passive"))
      (node (ref "T2") (pin "2") (pinfunction "E_2") (pintype "passive"))
    )
    (net (code "82") (name "RXD0") (class "Default")
      (node (ref "ESP32") (pin "34") (pinfunction "RXD0/IO3_34") (pintype "bidirectional"))
      (node (ref "JP2") (pin "3") (pinfunction "3_3") (pintype "passive"))
      (node (ref "R5") (pin "2") (pinfunction "2_2") (pintype "passive"))
    )
    (net (code "83") (name "RXLED") (class "Default")
      (node (ref "IC1") (pin "13") (pinfunction "RXLED/IO1_13") (pintype "bidirectional"))
      (node (ref "RX") (pin "C") (pinfunction "C_C") (pintype "passive"))
    )
    (net (code "84") (name "SCK") (class "Default")
      (node (ref "ESP32") (pin "20") (pinfunction "SCK/IO6_20") (pintype "bidirectional"))
    )
    (net (code "85") (name "SD0") (class "Default")
      (node (ref "ESP32") (pin "21") (pinfunction "SDO/IO7_21") (pintype "bidirectional"))
    )
    (net (code "86") (name "SD1") (class "Default")
      (node (ref "ESP32") (pin "22") (pinfunction "SDI/IO8_22") (pintype "bidirectional"))
    )
    (net (code "87") (name "SD2") (class "Default")
      (node (ref "ESP32") (pin "17") (pinfunction "SHD/IO9_17") (pintype "bidirectional"))
    )
    (net (code "88") (name "SD3") (class "Default")
      (node (ref "ESP32") (pin "18") (pinfunction "SWP/IO10_18") (pintype "bidirectional"))
    )
    (net (code "89") (name "SET_V++") (class "Default")
      (node (ref "JP2") (pin "13") (pinfunction "13_13") (pintype "passive"))
      (node (ref "R43") (pin "2") (pinfunction "2_2") (pintype "passive"))
    )
    (net (code "90") (name "SVN") (class "Default")
      (node (ref "ESP32") (pin "5") (pinfunction "SVN/I039/A1C3_5") (pintype "bidirectional"))
      (node (ref "JP2") (pin "6") (pinfunction "6_6") (pintype "passive"))
    )
    (net (code "91") (name "SVP") (class "Default")
      (node (ref "ESP32") (pin "4") (pinfunction "SVP/I036/A1C0_4") (pintype "bidirectional"))
      (node (ref "JP2") (pin "5") (pinfunction "5_5") (pintype "passive"))
    )
    (net (code "92") (name "TXD0") (class "Default")
      (node (ref "ESP32") (pin "35") (pinfunction "TXD0/IO1_35") (pintype "bidirectional"))
      (node (ref "JP2") (pin "2") (pinfunction "2_2") (pintype "passive"))
      (node (ref "R46") (pin "2") (pinfunction "2_2") (pintype "passive"))
    )
    (net (code "93") (name "TXLED") (class "Default")
      (node (ref "IC1") (pin "14") (pinfunction "TXLED/IO0_14") (pintype "bidirectional"))
      (node (ref "TX") (pin "C") (pinfunction "C_C") (pintype "passive"))
    )
    (net (code "94") (name "V++") (class "Default")
      (node (ref "C21") (pin "1") (pinfunction "1_1") (pintype "passive"))
      (node (ref "C22") (pin "1") (pinfunction "1_1") (pintype "passive"))
      (node (ref "D1") (pin "C") (pinfunction "C_C") (pintype "passive"))
      (node (ref "IC3") (pin "4") (pinfunction "EN_4") (pintype "bidirectional"))
      (node (ref "IC3") (pin "5") (pinfunction "VIN_5") (pintype "power_in"))
      (node (ref "JP2") (pin "12") (pinfunction "12_12") (pintype "passive"))
      (node (ref "L1") (pin "2") (pinfunction "2_2") (pintype "passive"))
      (node (ref "R39") (pin "1") (pinfunction "1_1") (pintype "passive"))
    )
    (net (code "95") (name "YELLOW") (class "Default")
      (node (ref "R22") (pin "1") (pinfunction "1_1") (pintype "passive"))
      (node (ref "U$1") (pin "2") (pinfunction "LED2/~{INTSEL}_2") (pintype "bidirectional"))
    )
    (net (code "96") (name "unconnected-(ESP32-NC-Pad32)") (class "Default")
      (node (ref "ESP32") (pin "32") (pinfunction "NC_32") (pintype "bidirectional"))
    )
    (net (code "97") (name "unconnected-(IC1-CLK{slash}~{RI}-Pad1)") (class "Default")
      (node (ref "IC1") (pin "1") (pinfunction "CLK/~{RI}_1") (pintype "bidirectional"))
    )
    (net (code "98") (name "unconnected-(IC1-RS485{slash}IO2-Pad12)") (class "Default")
      (node (ref "IC1") (pin "12") (pinfunction "RS485/IO2_12") (pintype "bidirectional"))
    )
    (net (code "99") (name "unconnected-(IC1-SUSPEND-Pad17)") (class "Default")
      (node (ref "IC1") (pin "17") (pinfunction "SUSPEND_17") (pintype "bidirectional"))
    )
    (net (code "100") (name "unconnected-(IC1-WAKEUP{slash}IO3-Pad11)") (class "Default")
      (node (ref "IC1") (pin "11") (pinfunction "WAKEUP/IO3_11") (pintype "bidirectional"))
    )
    (net (code "101") (name "unconnected-(IC1-~{CTS}-Pad18)") (class "Default")
      (node (ref "IC1") (pin "18") (pinfunction "~{CTS}_18") (pintype "bidirectional"))
    )
    (net (code "102") (name "unconnected-(IC1-~{DCD}-Pad24)") (class "Default")
      (node (ref "IC1") (pin "24") (pinfunction "~{DCD}_24") (pintype "bidirectional"))
    )
    (net (code "103") (name "unconnected-(IC1-~{DSR}-Pad22)") (class "Default")
      (node (ref "IC1") (pin "22") (pinfunction "~{DSR}_22") (pintype "bidirectional"))
    )
    (net (code "104") (name "unconnected-(IC1-~{SUSPEND}-Pad15)") (class "Default")
      (node (ref "IC1") (pin "15") (pinfunction "~{SUSPEND}_15") (pintype "bidirectional"))
    )
    (net (code "105") (name "unconnected-(U$1-XTAL2-Pad4)") (class "Default")
      (node (ref "U$1") (pin "4") (pinfunction "XTAL2_4") (pintype "bidirectional"))
    )
    (net (code "106") (name "unconnected-(U1-PG-Pad6)") (class "Default")
      (node (ref "U1") (pin "6") (pinfunction "PG_6") (pintype "bidirectional"))
    )
    (net (code "107") (name "unconnected-(X5-Pad4)") (class "Default")
      (node (ref "X5") (pin "4") (pinfunction "4_4") (pintype "input"))
    )
  )
)
